# dual_tdc.net
KiCad netlist of a schematic drawn in EAGLE
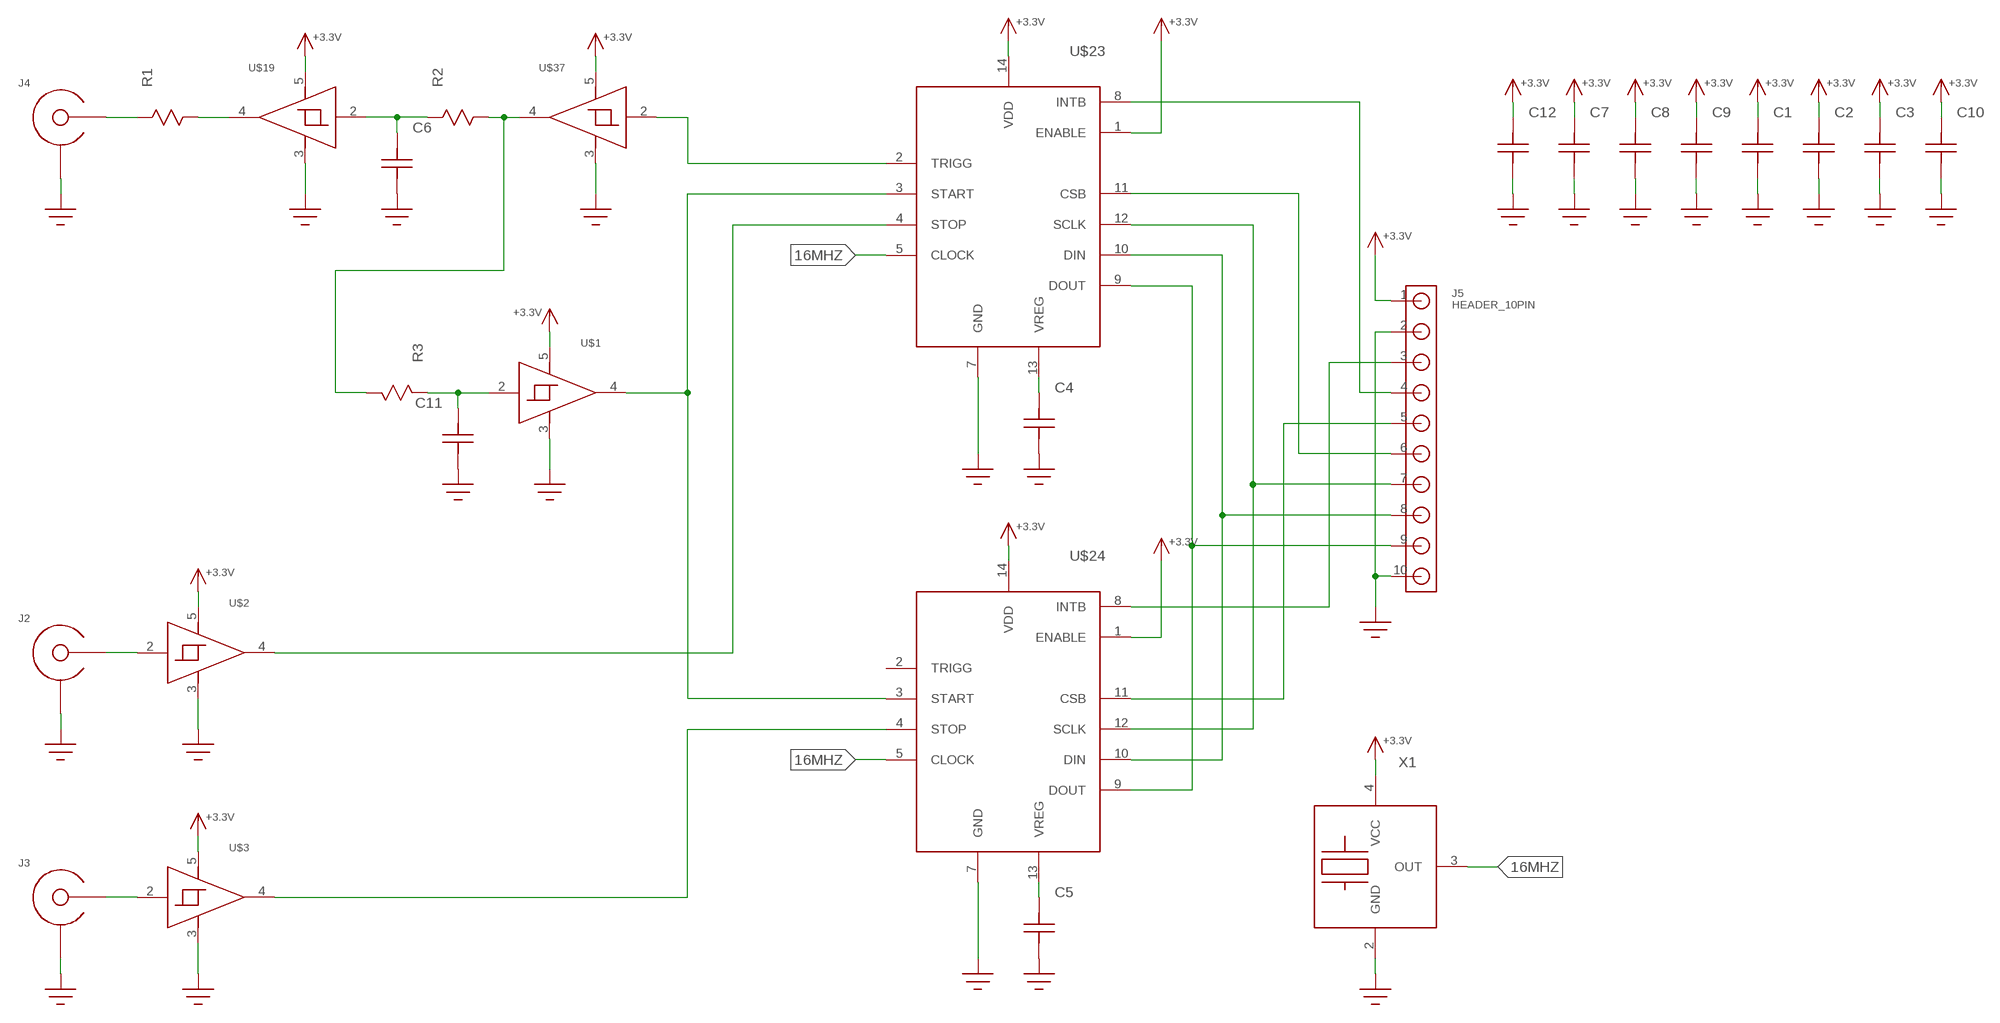
[diagram p0: schematic, sheet 1]

(export (version "E")
  (design (tool "Eeschema 10.0.6"))
  (components
    (comp (ref "C1")
      (value "C0603")
      (footprint "eagle-import:C0603")
      (libsource (lib "eagle-import") (part "C0603"))
    )
    (comp (ref "C2")
      (value "C0603")
      (footprint "eagle-import:C0603")
      (libsource (lib "eagle-import") (part "C0603"))
    )
    (comp (ref "C3")
      (value "C0603")
      (footprint "eagle-import:C0603")
      (libsource (lib "eagle-import") (part "C0603"))
    )
    (comp (ref "C4")
      (value "C0805")
      (footprint "eagle-import:0805")
      (libsource (lib "eagle-import") (part "C0805"))
    )
    (comp (ref "C5")
      (value "C0805")
      (footprint "eagle-import:0805")
      (libsource (lib "eagle-import") (part "C0805"))
    )
    (comp (ref "C6")
      (value "C0603")
      (footprint "eagle-import:C0603")
      (libsource (lib "eagle-import") (part "C0603"))
    )
    (comp (ref "C7")
      (value "C0603")
      (footprint "eagle-import:C0603")
      (libsource (lib "eagle-import") (part "C0603"))
    )
    (comp (ref "C8")
      (value "C0603")
      (footprint "eagle-import:C0603")
      (libsource (lib "eagle-import") (part "C0603"))
    )
    (comp (ref "C9")
      (value "C0603")
      (footprint "eagle-import:C0603")
      (libsource (lib "eagle-import") (part "C0603"))
    )
    (comp (ref "C10")
      (value "C0603")
      (footprint "eagle-import:C0603")
      (libsource (lib "eagle-import") (part "C0603"))
    )
    (comp (ref "C11")
      (value "C0603")
      (footprint "eagle-import:C0603")
      (libsource (lib "eagle-import") (part "C0603"))
    )
    (comp (ref "C12")
      (value "C0603")
      (footprint "eagle-import:C0603")
      (libsource (lib "eagle-import") (part "C0603"))
    )
    (comp (ref "J2")
      (value "EDGE_LAUNCH_JACK")
      (footprint "eagle-import:EDGE_LAUNCH_RF_CON")
      (libsource (lib "eagle-import") (part "EDGE_LAUNCH_JACK"))
    )
    (comp (ref "J3")
      (value "EDGE_LAUNCH_JACK")
      (footprint "eagle-import:EDGE_LAUNCH_RF_CON")
      (libsource (lib "eagle-import") (part "EDGE_LAUNCH_JACK"))
    )
    (comp (ref "J4")
      (value "EDGE_LAUNCH_JACK")
      (footprint "eagle-import:EDGE_LAUNCH_RF_CON")
      (libsource (lib "eagle-import") (part "EDGE_LAUNCH_JACK"))
    )
    (comp (ref "J5")
      (value "HEADER_10PIN")
      (footprint "eagle-import:HEADER_10PIN")
      (libsource (lib "eagle-import") (part "HEADER_10PIN"))
    )
    (comp (ref "R1")
      (value "R0805")
      (footprint "eagle-import:R0805")
      (libsource (lib "eagle-import") (part "R0805"))
    )
    (comp (ref "R2")
      (value "R0603")
      (footprint "eagle-import:R0603")
      (libsource (lib "eagle-import") (part "R0603"))
    )
    (comp (ref "R3")
      (value "R0603")
      (footprint "eagle-import:R0603")
      (libsource (lib "eagle-import") (part "R0603"))
    )
    (comp (ref "U$1")
      (value "74LVC1G17")
      (footprint "eagle-import:SOT23-5")
      (libsource (lib "eagle-import") (part "74LVC1G17"))
    )
    (comp (ref "U$2")
      (value "74LVC1G17")
      (footprint "eagle-import:SOT23-5")
      (libsource (lib "eagle-import") (part "74LVC1G17"))
    )
    (comp (ref "U$3")
      (value "74LVC1G17")
      (footprint "eagle-import:SOT23-5")
      (libsource (lib "eagle-import") (part "74LVC1G17"))
    )
    (comp (ref "U$19")
      (value "74LVC1G17")
      (footprint "eagle-import:SOT23-5")
      (libsource (lib "eagle-import") (part "74LVC1G17"))
    )
    (comp (ref "U$23")
      (value "TDC7200TSSOP")
      (footprint "eagle-import:TSSOP14")
      (libsource (lib "eagle-import") (part "TDC7200TSSOP"))
    )
    (comp (ref "U$24")
      (value "TDC7200TSSOP")
      (footprint "eagle-import:TSSOP14")
      (libsource (lib "eagle-import") (part "TDC7200TSSOP"))
    )
    (comp (ref "U$37")
      (value "74LVC1G17")
      (footprint "eagle-import:SOT23-5")
      (libsource (lib "eagle-import") (part "74LVC1G17"))
    )
    (comp (ref "X1")
      (value "XTAL_OSC")
      (footprint "eagle-import:XTAL_3.2X5")
      (libsource (lib "eagle-import") (part "XTAL_OSC"))
    )
  )
  (nets
    (net (code "1") (name "+3.3V") (class "Default")
      (node (ref "C1") (pin "P$2") (pinfunction "P$2_P$2") (pintype "bidirectional"))
      (node (ref "C10") (pin "P$2") (pinfunction "P$2_P$2") (pintype "bidirectional"))
      (node (ref "C12") (pin "P$2") (pinfunction "P$2_P$2") (pintype "bidirectional"))
      (node (ref "C2") (pin "P$2") (pinfunction "P$2_P$2") (pintype "bidirectional"))
      (node (ref "C3") (pin "P$2") (pinfunction "P$2_P$2") (pintype "bidirectional"))
      (node (ref "C7") (pin "P$2") (pinfunction "P$2_P$2") (pintype "bidirectional"))
      (node (ref "C8") (pin "P$2") (pinfunction "P$2_P$2") (pintype "bidirectional"))
      (node (ref "C9") (pin "P$2") (pinfunction "P$2_P$2") (pintype "bidirectional"))
      (node (ref "J5") (pin "1") (pinfunction "1_1") (pintype "bidirectional"))
      (node (ref "U$1") (pin "5") (pinfunction "VCC_5") (pintype "bidirectional"))
      (node (ref "U$19") (pin "5") (pinfunction "VCC_5") (pintype "bidirectional"))
      (node (ref "U$2") (pin "5") (pinfunction "VCC_5") (pintype "bidirectional"))
      (node (ref "U$23") (pin "1") (pinfunction "ENABLE_1") (pintype "bidirectional"))
      (node (ref "U$23") (pin "14") (pinfunction "VDD_14") (pintype "bidirectional"))
      (node (ref "U$24") (pin "1") (pinfunction "ENABLE_1") (pintype "bidirectional"))
      (node (ref "U$24") (pin "14") (pinfunction "VDD_14") (pintype "bidirectional"))
      (node (ref "U$3") (pin "5") (pinfunction "VCC_5") (pintype "bidirectional"))
      (node (ref "U$37") (pin "5") (pinfunction "VCC_5") (pintype "bidirectional"))
      (node (ref "X1") (pin "4") (pinfunction "VCC_4") (pintype "bidirectional"))
    )
    (net (code "2") (name "16MHZ") (class "Default")
      (node (ref "U$23") (pin "5") (pinfunction "CLOCK_5") (pintype "bidirectional"))
      (node (ref "U$24") (pin "5") (pinfunction "CLOCK_5") (pintype "bidirectional"))
      (node (ref "X1") (pin "3") (pinfunction "OUT_3") (pintype "bidirectional"))
    )
    (net (code "3") (name "GND") (class "Default")
      (node (ref "C1") (pin "P$1") (pinfunction "P$1_P$1") (pintype "bidirectional"))
      (node (ref "C10") (pin "P$1") (pinfunction "P$1_P$1") (pintype "bidirectional"))
      (node (ref "C11") (pin "P$1") (pinfunction "P$1_P$1") (pintype "bidirectional"))
      (node (ref "C12") (pin "P$1") (pinfunction "P$1_P$1") (pintype "bidirectional"))
      (node (ref "C2") (pin "P$1") (pinfunction "P$1_P$1") (pintype "bidirectional"))
      (node (ref "C3") (pin "P$1") (pinfunction "P$1_P$1") (pintype "bidirectional"))
      (node (ref "C4") (pin "P$1") (pinfunction "P$1_P$1") (pintype "bidirectional"))
      (node (ref "C5") (pin "P$1") (pinfunction "P$1_P$1") (pintype "bidirectional"))
      (node (ref "C6") (pin "P$1") (pinfunction "P$1_P$1") (pintype "bidirectional"))
      (node (ref "C7") (pin "P$1") (pinfunction "P$1_P$1") (pintype "bidirectional"))
      (node (ref "C8") (pin "P$1") (pinfunction "P$1_P$1") (pintype "bidirectional"))
      (node (ref "C9") (pin "P$1") (pinfunction "P$1_P$1") (pintype "bidirectional"))
      (node (ref "J2") (pin "GND@1") (pinfunction "SHIELD_GND@1") (pintype "bidirectional"))
      (node (ref "J2") (pin "GND@10") (pinfunction "SHIELD_GND@10") (pintype "bidirectional"))
      (node (ref "J2") (pin "GND@11") (pinfunction "SHIELD_GND@11") (pintype "bidirectional"))
      (node (ref "J2") (pin "GND@12") (pinfunction "SHIELD_GND@12") (pintype "bidirectional"))
      (node (ref "J2") (pin "GND@2") (pinfunction "SHIELD_GND@2") (pintype "bidirectional"))
      (node (ref "J2") (pin "GND@3") (pinfunction "SHIELD_GND@3") (pintype "bidirectional"))
      (node (ref "J2") (pin "GND@4") (pinfunction "SHIELD_GND@4") (pintype "bidirectional"))
      (node (ref "J2") (pin "GND@5") (pinfunction "SHIELD_GND@5") (pintype "bidirectional"))
      (node (ref "J2") (pin "GND@6") (pinfunction "SHIELD_GND@6") (pintype "bidirectional"))
      (node (ref "J2") (pin "GND@7") (pinfunction "SHIELD_GND@7") (pintype "bidirectional"))
      (node (ref "J2") (pin "GND@8") (pinfunction "SHIELD_GND@8") (pintype "bidirectional"))
      (node (ref "J2") (pin "GND@9") (pinfunction "SHIELD_GND@9") (pintype "bidirectional"))
      (node (ref "J2") (pin "SHIELD@1") (pinfunction "SHIELD_SHIELD@1") (pintype "bidirectional"))
      (node (ref "J2") (pin "SHIELD@2") (pinfunction "SHIELD_SHIELD@2") (pintype "bidirectional"))
      (node (ref "J3") (pin "GND@1") (pinfunction "SHIELD_GND@1") (pintype "bidirectional"))
      (node (ref "J3") (pin "GND@10") (pinfunction "SHIELD_GND@10") (pintype "bidirectional"))
      (node (ref "J3") (pin "GND@11") (pinfunction "SHIELD_GND@11") (pintype "bidirectional"))
      (node (ref "J3") (pin "GND@12") (pinfunction "SHIELD_GND@12") (pintype "bidirectional"))
      (node (ref "J3") (pin "GND@2") (pinfunction "SHIELD_GND@2") (pintype "bidirectional"))
      (node (ref "J3") (pin "GND@3") (pinfunction "SHIELD_GND@3") (pintype "bidirectional"))
      (node (ref "J3") (pin "GND@4") (pinfunction "SHIELD_GND@4") (pintype "bidirectional"))
      (node (ref "J3") (pin "GND@5") (pinfunction "SHIELD_GND@5") (pintype "bidirectional"))
      (node (ref "J3") (pin "GND@6") (pinfunction "SHIELD_GND@6") (pintype "bidirectional"))
      (node (ref "J3") (pin "GND@7") (pinfunction "SHIELD_GND@7") (pintype "bidirectional"))
      (node (ref "J3") (pin "GND@8") (pinfunction "SHIELD_GND@8") (pintype "bidirectional"))
      (node (ref "J3") (pin "GND@9") (pinfunction "SHIELD_GND@9") (pintype "bidirectional"))
      (node (ref "J3") (pin "SHIELD@1") (pinfunction "SHIELD_SHIELD@1") (pintype "bidirectional"))
      (node (ref "J3") (pin "SHIELD@2") (pinfunction "SHIELD_SHIELD@2") (pintype "bidirectional"))
      (node (ref "J4") (pin "GND@1") (pinfunction "SHIELD_GND@1") (pintype "bidirectional"))
      (node (ref "J4") (pin "GND@10") (pinfunction "SHIELD_GND@10") (pintype "bidirectional"))
      (node (ref "J4") (pin "GND@11") (pinfunction "SHIELD_GND@11") (pintype "bidirectional"))
      (node (ref "J4") (pin "GND@12") (pinfunction "SHIELD_GND@12") (pintype "bidirectional"))
      (node (ref "J4") (pin "GND@2") (pinfunction "SHIELD_GND@2") (pintype "bidirectional"))
      (node (ref "J4") (pin "GND@3") (pinfunction "SHIELD_GND@3") (pintype "bidirectional"))
      (node (ref "J4") (pin "GND@4") (pinfunction "SHIELD_GND@4") (pintype "bidirectional"))
      (node (ref "J4") (pin "GND@5") (pinfunction "SHIELD_GND@5") (pintype "bidirectional"))
      (node (ref "J4") (pin "GND@6") (pinfunction "SHIELD_GND@6") (pintype "bidirectional"))
      (node (ref "J4") (pin "GND@7") (pinfunction "SHIELD_GND@7") (pintype "bidirectional"))
      (node (ref "J4") (pin "GND@8") (pinfunction "SHIELD_GND@8") (pintype "bidirectional"))
      (node (ref "J4") (pin "GND@9") (pinfunction "SHIELD_GND@9") (pintype "bidirectional"))
      (node (ref "J4") (pin "SHIELD@1") (pinfunction "SHIELD_SHIELD@1") (pintype "bidirectional"))
      (node (ref "J4") (pin "SHIELD@2") (pinfunction "SHIELD_SHIELD@2") (pintype "bidirectional"))
      (node (ref "J5") (pin "10") (pinfunction "10_10") (pintype "bidirectional"))
      (node (ref "J5") (pin "2") (pinfunction "2_2") (pintype "bidirectional"))
      (node (ref "U$1") (pin "3") (pinfunction "GND_3") (pintype "bidirectional"))
      (node (ref "U$19") (pin "3") (pinfunction "GND_3") (pintype "bidirectional"))
      (node (ref "U$2") (pin "3") (pinfunction "GND_3") (pintype "bidirectional"))
      (node (ref "U$23") (pin "7") (pinfunction "GND_7") (pintype "bidirectional"))
      (node (ref "U$24") (pin "7") (pinfunction "GND_7") (pintype "bidirectional"))
      (node (ref "U$3") (pin "3") (pinfunction "GND_3") (pintype "bidirectional"))
      (node (ref "U$37") (pin "3") (pinfunction "GND_3") (pintype "bidirectional"))
      (node (ref "X1") (pin "2") (pinfunction "GND_2") (pintype "bidirectional"))
    )
    (net (code "4") (name "Net-(R1-P$3)") (class "Default")
      (node (ref "J4") (pin "CENTER") (pinfunction "CENTER_CENTER") (pintype "bidirectional"))
      (node (ref "R1") (pin "P$1") (pinfunction "P$3_P$1") (pintype "bidirectional"))
    )
    (net (code "5") (name "Net-(R1-P$4)") (class "Default")
      (node (ref "R1") (pin "P$2") (pinfunction "P$4_P$2") (pintype "bidirectional"))
      (node (ref "U$19") (pin "4") (pinfunction "OUT_4") (pintype "bidirectional"))
    )
    (net (code "6") (name "Net-(R2-P$3)") (class "Default")
      (node (ref "C6") (pin "P$2") (pinfunction "P$2_P$2") (pintype "bidirectional"))
      (node (ref "R2") (pin "P$1") (pinfunction "P$3_P$1") (pintype "bidirectional"))
      (node (ref "U$19") (pin "2") (pinfunction "IN_2") (pintype "bidirectional"))
    )
    (net (code "7") (name "Net-(R2-P$4)") (class "Default")
      (node (ref "R2") (pin "P$2") (pinfunction "P$4_P$2") (pintype "bidirectional"))
      (node (ref "R3") (pin "P$2") (pinfunction "P$4_P$2") (pintype "bidirectional"))
      (node (ref "U$37") (pin "4") (pinfunction "OUT_4") (pintype "bidirectional"))
    )
    (net (code "8") (name "Net-(R3-P$3)") (class "Default")
      (node (ref "C11") (pin "P$2") (pinfunction "P$2_P$2") (pintype "bidirectional"))
      (node (ref "R3") (pin "P$1") (pinfunction "P$3_P$1") (pintype "bidirectional"))
      (node (ref "U$1") (pin "2") (pinfunction "IN_2") (pintype "bidirectional"))
    )
    (net (code "9") (name "Net-(U$1-OUT)") (class "Default")
      (node (ref "U$1") (pin "4") (pinfunction "OUT_4") (pintype "bidirectional"))
      (node (ref "U$23") (pin "3") (pinfunction "START_3") (pintype "bidirectional"))
      (node (ref "U$24") (pin "3") (pinfunction "START_3") (pintype "bidirectional"))
    )
    (net (code "10") (name "Net-(U$2-IN)") (class "Default")
      (node (ref "J2") (pin "CENTER") (pinfunction "CENTER_CENTER") (pintype "bidirectional"))
      (node (ref "U$2") (pin "2") (pinfunction "IN_2") (pintype "bidirectional"))
    )
    (net (code "11") (name "Net-(U$2-OUT)") (class "Default")
      (node (ref "U$2") (pin "4") (pinfunction "OUT_4") (pintype "bidirectional"))
      (node (ref "U$23") (pin "4") (pinfunction "STOP_4") (pintype "bidirectional"))
    )
    (net (code "12") (name "Net-(U$3-IN)") (class "Default")
      (node (ref "J3") (pin "CENTER") (pinfunction "CENTER_CENTER") (pintype "bidirectional"))
      (node (ref "U$3") (pin "2") (pinfunction "IN_2") (pintype "bidirectional"))
    )
    (net (code "13") (name "Net-(U$23-CSB)") (class "Default")
      (node (ref "J5") (pin "6") (pinfunction "6_6") (pintype "bidirectional"))
      (node (ref "U$23") (pin "11") (pinfunction "CSB_11") (pintype "bidirectional"))
    )
    (net (code "14") (name "Net-(U$23-DIN)") (class "Default")
      (node (ref "J5") (pin "8") (pinfunction "8_8") (pintype "bidirectional"))
      (node (ref "U$23") (pin "10") (pinfunction "DIN_10") (pintype "bidirectional"))
      (node (ref "U$24") (pin "10") (pinfunction "DIN_10") (pintype "bidirectional"))
    )
    (net (code "15") (name "Net-(U$23-DOUT)") (class "Default")
      (node (ref "J5") (pin "9") (pinfunction "9_9") (pintype "bidirectional"))
      (node (ref "U$23") (pin "9") (pinfunction "DOUT_9") (pintype "bidirectional"))
      (node (ref "U$24") (pin "9") (pinfunction "DOUT_9") (pintype "bidirectional"))
    )
    (net (code "16") (name "Net-(U$23-INTB)") (class "Default")
      (node (ref "J5") (pin "4") (pinfunction "4_4") (pintype "bidirectional"))
      (node (ref "U$23") (pin "8") (pinfunction "INTB_8") (pintype "bidirectional"))
    )
    (net (code "17") (name "Net-(U$23-SCLK)") (class "Default")
      (node (ref "J5") (pin "7") (pinfunction "7_7") (pintype "bidirectional"))
      (node (ref "U$23") (pin "12") (pinfunction "SCLK_12") (pintype "bidirectional"))
      (node (ref "U$24") (pin "12") (pinfunction "SCLK_12") (pintype "bidirectional"))
    )
    (net (code "18") (name "Net-(U$23-TRIGG)") (class "Default")
      (node (ref "U$23") (pin "2") (pinfunction "TRIGG_2") (pintype "bidirectional"))
      (node (ref "U$37") (pin "2") (pinfunction "IN_2") (pintype "bidirectional"))
    )
    (net (code "19") (name "Net-(U$23-VREG)") (class "Default")
      (node (ref "C4") (pin "P$2") (pinfunction "P$2_P$2") (pintype "bidirectional"))
      (node (ref "U$23") (pin "13") (pinfunction "VREG_13") (pintype "bidirectional"))
    )
    (net (code "20") (name "Net-(U$24-CSB)") (class "Default")
      (node (ref "J5") (pin "5") (pinfunction "5_5") (pintype "bidirectional"))
      (node (ref "U$24") (pin "11") (pinfunction "CSB_11") (pintype "bidirectional"))
    )
    (net (code "21") (name "Net-(U$24-INTB)") (class "Default")
      (node (ref "J5") (pin "3") (pinfunction "3_3") (pintype "bidirectional"))
      (node (ref "U$24") (pin "8") (pinfunction "INTB_8") (pintype "bidirectional"))
    )
    (net (code "22") (name "Net-(U$24-STOP)") (class "Default")
      (node (ref "U$24") (pin "4") (pinfunction "STOP_4") (pintype "bidirectional"))
      (node (ref "U$3") (pin "4") (pinfunction "OUT_4") (pintype "bidirectional"))
    )
    (net (code "23") (name "Net-(U$24-VREG)") (class "Default")
      (node (ref "C5") (pin "P$2") (pinfunction "P$2_P$2") (pintype "bidirectional"))
      (node (ref "U$24") (pin "13") (pinfunction "VREG_13") (pintype "bidirectional"))
    )
    (net (code "24") (name "unconnected-(U$24-TRIGG-Pad2)") (class "Default")
      (node (ref "U$24") (pin "2") (pinfunction "TRIGG_2") (pintype "bidirectional"))
    )
  )
)
